# MACH_TAO_XUNG.net
KiCad netlist of a schematic drawn in Altium Designer
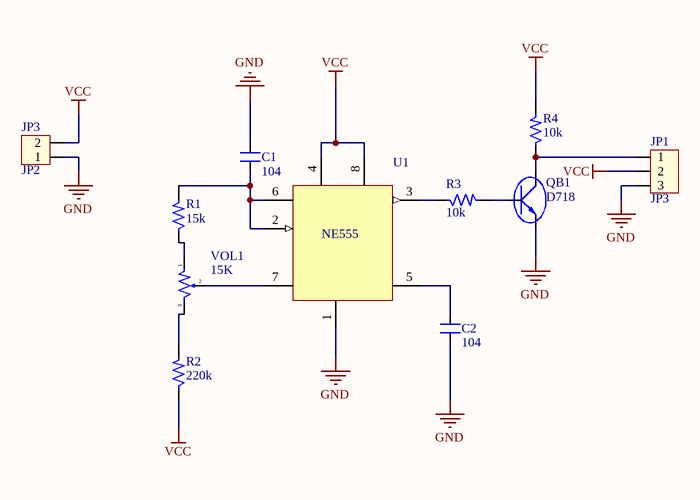
[diagram p0: MACH TAO XUNG.SchDoc]

(export (version "E")
  (design (tool "Eeschema 10.0.6"))
  (components
    (comp (ref "C1")
      (value "104")
      (footprint "SM-0805")
      (description "Cap SMD")
      (libsource (lib "syhaunguyen") (part "CM"))
    )
    (comp (ref "C2")
      (value "104")
      (footprint "SM-0805")
      (description "Cap SMD")
      (libsource (lib "syhaunguyen") (part "CM"))
    )
    (comp (ref "JP1")
      (value "JP3")
      (footprint "syhaunguyen:CON3")
      (description "Connector 3")
      (libsource (lib "syhaunguyen") (part "Con3"))
    )
    (comp (ref "JP3")
      (value "JP2")
      (footprint "syhaunguyen:CON2")
      (description "Connector 2")
      (libsource (lib "syhaunguyen") (part "Con2"))
    )
    (comp (ref "QB1")
      (value "D718")
      (footprint "QTO-247")
      (description "Transistor Power Supply")
      (libsource (lib "syhaunguyen") (part "D718"))
    )
    (comp (ref "R1")
      (value "15k")
      (footprint "SM-0805")
      (description "Resistor 1/4W")
      (libsource (lib "syhaunguyen") (part "R"))
    )
    (comp (ref "R2")
      (value "220k")
      (footprint "SM-0805")
      (description "Resistor 1/4W")
      (libsource (lib "syhaunguyen") (part "R"))
    )
    (comp (ref "R3")
      (value "10k")
      (footprint "SM-0805")
      (description "Resistor 1/4W")
      (libsource (lib "syhaunguyen") (part "R"))
    )
    (comp (ref "R4")
      (value "10k")
      (footprint "SM-0805")
      (description "Resistor 1/4W")
      (libsource (lib "syhaunguyen") (part "R"))
    )
    (comp (ref "U1") (value "NE555") (footprint "DIP8/W0.3K") (libsource (lib "Schlib1") (part "NE555")))
    (comp (ref "VOL1")
      (value "15K")
      (footprint "VOL_1")
      (description "Var Resistor")
      (libsource (lib "syhaunguyen") (part "VOL-S"))
    )
  )
  (nets
    (net (code "1") (name "GND") (class "Default")
      (node (ref "C1") (pin "2") (pinfunction "2_2") (pintype "passive"))
      (node (ref "C2") (pin "1") (pinfunction "1_1") (pintype "passive"))
      (node (ref "JP1") (pin "3") (pinfunction "3_3") (pintype "passive"))
      (node (ref "JP3") (pin "1") (pinfunction "1_1") (pintype "passive"))
      (node (ref "QB1") (pin "3") (pinfunction "E_3") (pintype "passive"))
      (node (ref "U1") (pin "1") (pintype "power_in"))
    )
    (net (code "2") (name "Net-(C1-Pad1)") (class "Default")
      (node (ref "C1") (pin "1") (pinfunction "1_1") (pintype "passive"))
      (node (ref "R1") (pin "2") (pinfunction "2_2") (pintype "passive"))
      (node (ref "U1") (pin "2") (pintype "input"))
      (node (ref "U1") (pin "6") (pintype "passive"))
    )
    (net (code "3") (name "Net-(C2-Pad2)") (class "Default")
      (node (ref "C2") (pin "2") (pinfunction "2_2") (pintype "passive"))
      (node (ref "U1") (pin "5") (pintype "passive"))
    )
    (net (code "4") (name "Net-(QB1-B)") (class "Default")
      (node (ref "QB1") (pin "1") (pinfunction "B_1") (pintype "passive"))
      (node (ref "R3") (pin "2") (pinfunction "2_2") (pintype "passive"))
    )
    (net (code "5") (name "Net-(QB1-C)") (class "Default")
      (node (ref "JP1") (pin "1") (pinfunction "1_1") (pintype "passive"))
      (node (ref "QB1") (pin "2") (pinfunction "C_2") (pintype "passive"))
      (node (ref "R4") (pin "1") (pinfunction "1_1") (pintype "passive"))
    )
    (net (code "6") (name "Net-(R1-Pad1)") (class "Default")
      (node (ref "R1") (pin "1") (pinfunction "1_1") (pintype "passive"))
      (node (ref "VOL1") (pin "1") (pinfunction "1_1") (pintype "passive"))
    )
    (net (code "7") (name "Net-(R2-Pad2)") (class "Default")
      (node (ref "R2") (pin "2") (pinfunction "2_2") (pintype "passive"))
      (node (ref "VOL1") (pin "3") (pinfunction "3_3") (pintype "passive"))
    )
    (net (code "8") (name "Net-(R3-Pad1)") (class "Default")
      (node (ref "R3") (pin "1") (pinfunction "1_1") (pintype "passive"))
      (node (ref "U1") (pin "3") (pintype "output"))
    )
    (net (code "9") (name "Net-(U1-Pad7)") (class "Default")
      (node (ref "U1") (pin "7") (pintype "passive"))
      (node (ref "VOL1") (pin "2") (pinfunction "2_2") (pintype "passive"))
    )
    (net (code "10") (name "VCC") (class "Default")
      (node (ref "JP1") (pin "2") (pinfunction "2_2") (pintype "passive"))
      (node (ref "JP3") (pin "2") (pinfunction "2_2") (pintype "passive"))
      (node (ref "R2") (pin "1") (pinfunction "1_1") (pintype "passive"))
      (node (ref "R4") (pin "2") (pinfunction "2_2") (pintype "passive"))
      (node (ref "U1") (pin "4") (pintype "power_in"))
      (node (ref "U1") (pin "8") (pintype "power_in"))
    )
  )
)
